# HF1R01.net
KiCad netlist of a schematic drawn in EAGLE
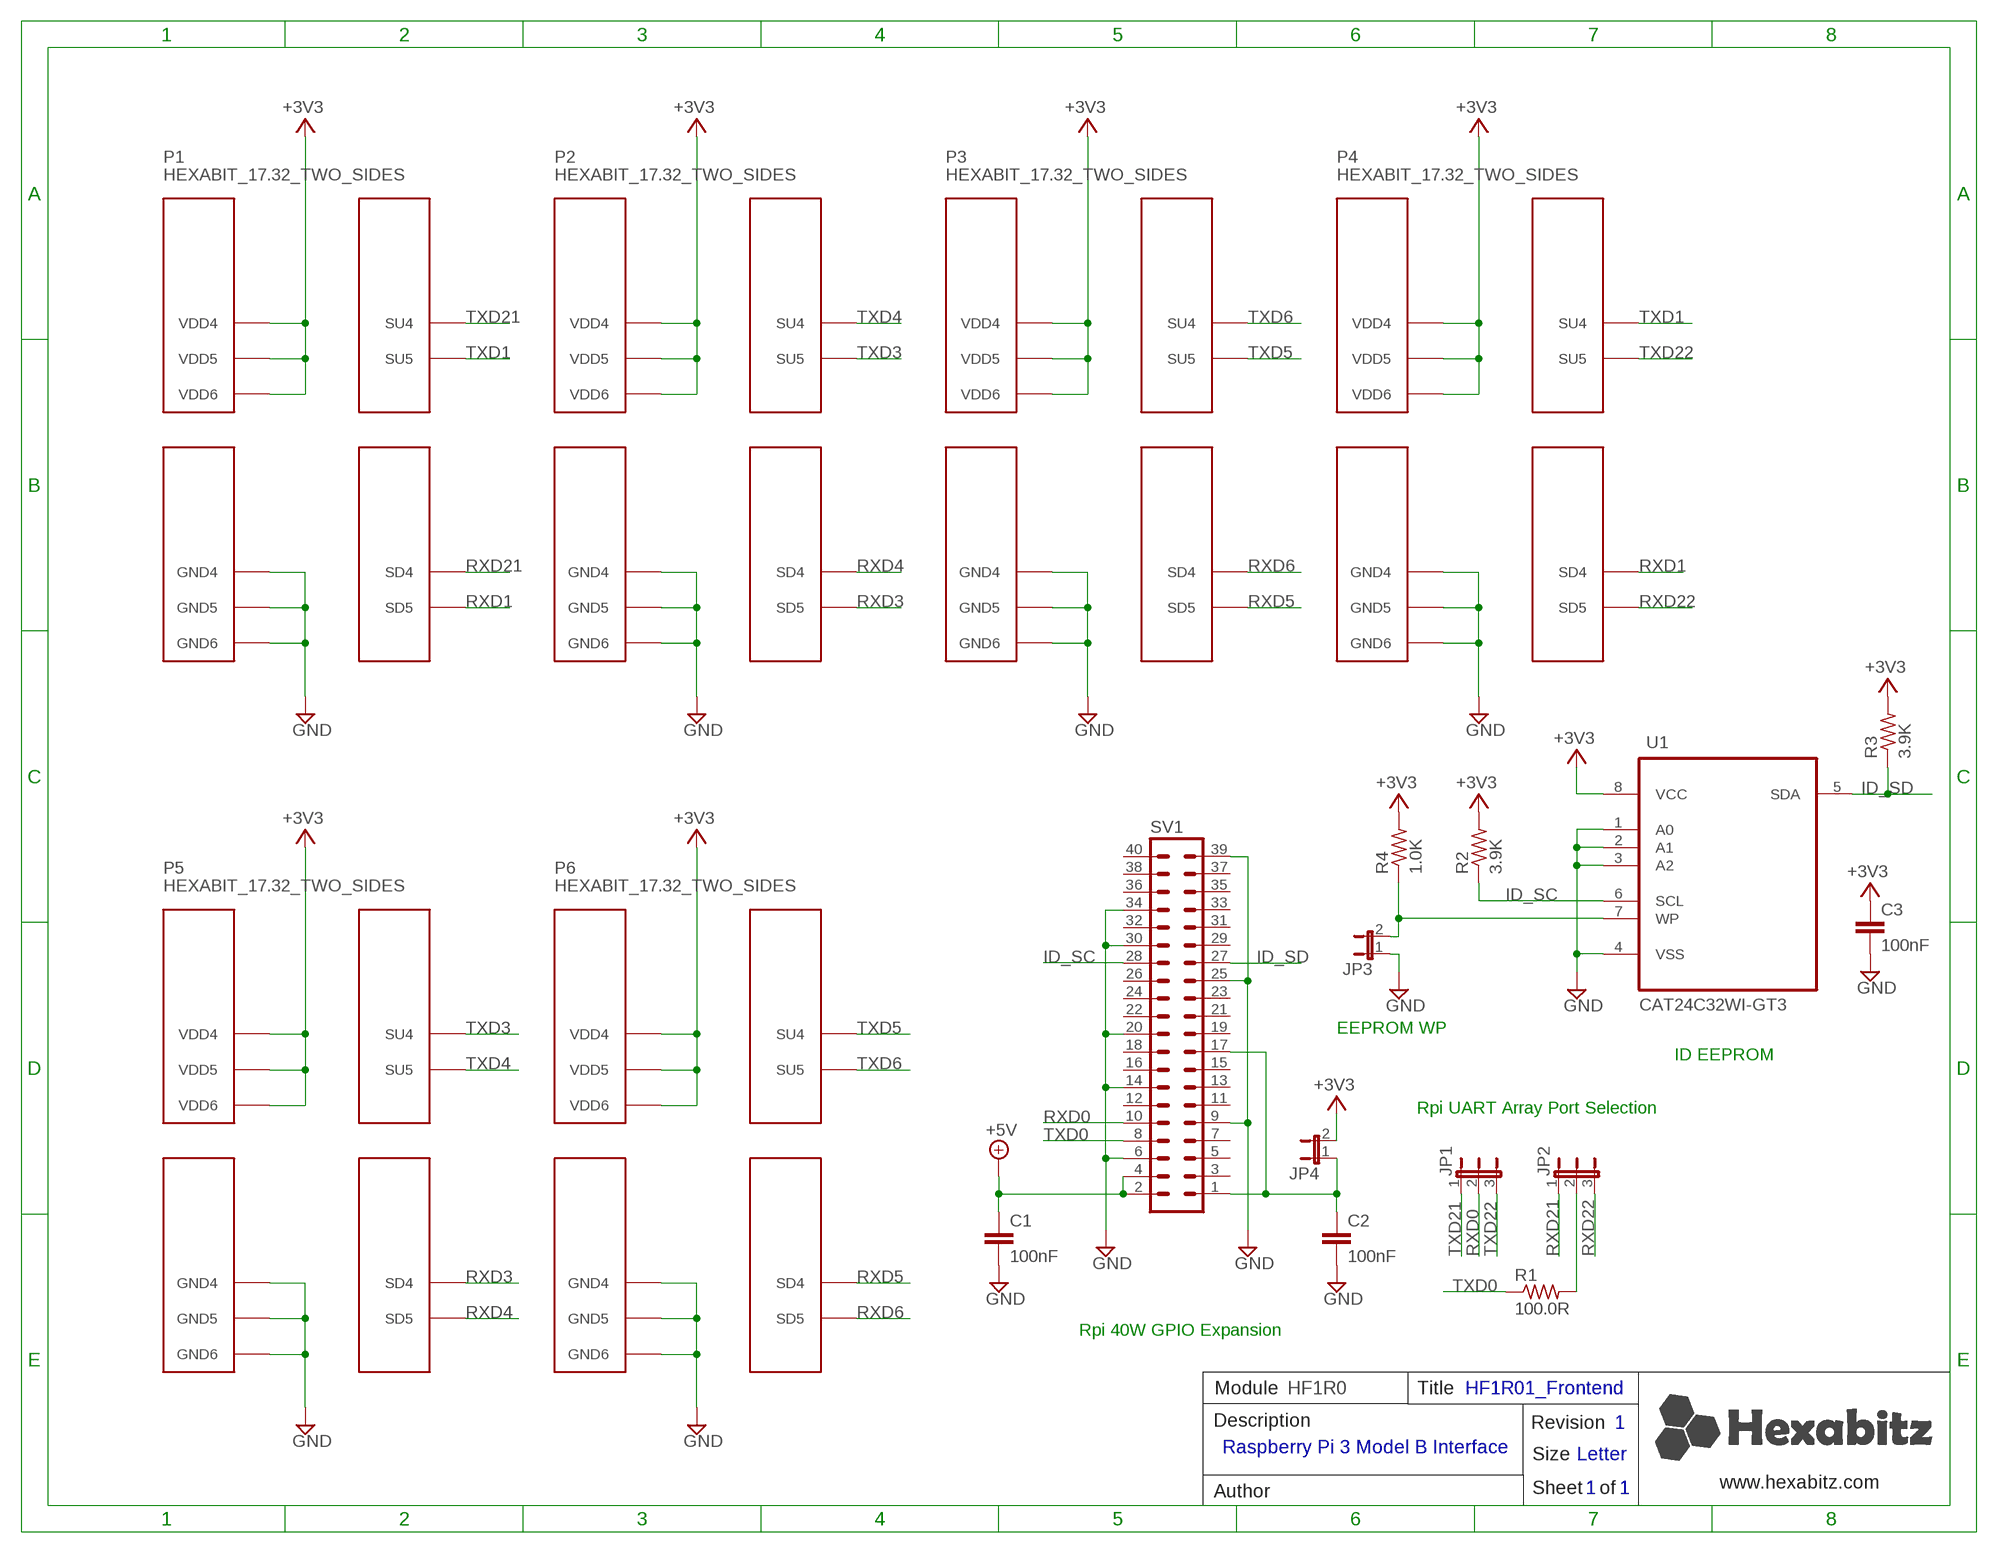
[diagram p0: schematic, sheet 1]

(export (version "E")
  (design (tool "Eeschema 10.0.6"))
  (components
    (comp (ref "C1")
      (value "100nF")
      (footprint "eagle-import:C-0603")
      (fields
        (field (name "CAPACITANCE") "100nF")
        (field (name "MFN") "KEMET")
        (field (name "MPN") "C0603C104K8RACTU")
        (field (name "OCTOPART_URL") "https://octopart.com/c0603c104k8ractu-kemet-145075?r=sp&s=9bS9ASSwSEqMCE9KBEQZ0g")
        (field (name "TOLERANCE") "10V")
        (field (name "VOLTAGE_RATING") "10%")
      )
      (libsource (lib "eagle-import") (part "C-0603"))
    )
    (comp (ref "C2")
      (value "100nF")
      (footprint "eagle-import:C-0603")
      (fields
        (field (name "CAPACITANCE") "100nF")
        (field (name "MFN") "KEMET")
        (field (name "MPN") "C0603C104K8RACTU")
        (field (name "OCTOPART_URL") "https://octopart.com/c0603c104k8ractu-kemet-145075?r=sp&s=9bS9ASSwSEqMCE9KBEQZ0g")
        (field (name "TOLERANCE") "10V")
        (field (name "VOLTAGE_RATING") "10%")
      )
      (libsource (lib "eagle-import") (part "C-0603"))
    )
    (comp (ref "C3")
      (value "100nF")
      (footprint "eagle-import:C-0603")
      (fields
        (field (name "CAPACITANCE") "100nF")
        (field (name "MFN") "KEMET")
        (field (name "MPN") "C0603C104K8RACTU")
        (field (name "OCTOPART_URL") "https://octopart.com/c0603c104k8ractu-kemet-145075?r=sp&s=9bS9ASSwSEqMCE9KBEQZ0g")
        (field (name "TOLERANCE") "10V")
        (field (name "VOLTAGE_RATING") "10%")
      )
      (libsource (lib "eagle-import") (part "C-0603"))
    )
    (comp (ref "JP1")
      (value "61300311121")
      (footprint "eagle-import:JP2")
      (libsource (lib "eagle-import") (part "JP2E"))
    )
    (comp (ref "JP2")
      (value "61300311121")
      (footprint "eagle-import:JP2")
      (libsource (lib "eagle-import") (part "JP2E"))
    )
    (comp (ref "JP3")
      (value "61300211121")
      (footprint "eagle-import:JP1")
      (libsource (lib "eagle-import") (part "JP1E"))
    )
    (comp (ref "JP4")
      (value "61300211121")
      (footprint "eagle-import:JP1")
      (libsource (lib "eagle-import") (part "JP1E"))
    )
    (comp (ref "P1")
      (value "HEXABIT_17.32_TWO_SIDES")
      (footprint "eagle-import:HEXABIT_17.32_TWO_SIDES")
      (libsource (lib "eagle-import") (part "HEXABIT_?_TWO_SIDES17.32"))
    )
    (comp (ref "P2")
      (value "HEXABIT_17.32_TWO_SIDES")
      (footprint "eagle-import:HEXABIT_17.32_TWO_SIDES")
      (libsource (lib "eagle-import") (part "HEXABIT_?_TWO_SIDES17.32"))
    )
    (comp (ref "P3")
      (value "HEXABIT_17.32_TWO_SIDES")
      (footprint "eagle-import:HEXABIT_17.32_TWO_SIDES")
      (libsource (lib "eagle-import") (part "HEXABIT_?_TWO_SIDES17.32"))
    )
    (comp (ref "P4")
      (value "HEXABIT_17.32_TWO_SIDES")
      (footprint "eagle-import:HEXABIT_17.32_TWO_SIDES")
      (libsource (lib "eagle-import") (part "HEXABIT_?_TWO_SIDES17.32"))
    )
    (comp (ref "P5")
      (value "HEXABIT_17.32_TWO_SIDES")
      (footprint "eagle-import:HEXABIT_17.32_TWO_SIDES")
      (libsource (lib "eagle-import") (part "HEXABIT_?_TWO_SIDES17.32"))
    )
    (comp (ref "P6")
      (value "HEXABIT_17.32_TWO_SIDES")
      (footprint "eagle-import:HEXABIT_17.32_TWO_SIDES")
      (libsource (lib "eagle-import") (part "HEXABIT_?_TWO_SIDES17.32"))
    )
    (comp (ref "R1")
      (value "100.0R")
      (footprint "eagle-import:R-0603")
      (fields
        (field (name "MFN") "Panasonic ")
        (field (name "MPN") "ERJ-PA3F1000V")
        (field (name "OCTOPART_URL") "https://octopart.com/erj-pa3f1000v-panasonic-51302178?r=sp&s=FtfQlVmZQ6G_o34px3VECw")
        (field (name "RESISTANCE") "100.0 Ohm")
        (field (name "TOLERANCE") "1%")
      )
      (libsource (lib "eagle-import") (part "R-0603"))
    )
    (comp (ref "R2")
      (value "3.9K")
      (footprint "eagle-import:R-0603")
      (fields
        (field (name "MFN") "Vishay")
        (field (name "MPN") "CRCW06033K90FKEA")
        (field (name "OCTOPART_URL") "https://octopart.com/crcw06033k90fkea-vishay-40019003?r=sp&s=g-tYgB-WSDSQxdPWmNeinA")
        (field (name "RESISTANCE") "3.9 kOhm")
        (field (name "TOLERANCE") "1%")
      )
      (libsource (lib "eagle-import") (part "R-0603"))
    )
    (comp (ref "R3")
      (value "3.9K")
      (footprint "eagle-import:R-0603")
      (fields
        (field (name "MFN") "Vishay")
        (field (name "MPN") "CRCW06033K90FKEA")
        (field (name "OCTOPART_URL") "https://octopart.com/crcw06033k90fkea-vishay-40019003?r=sp&s=g-tYgB-WSDSQxdPWmNeinA")
        (field (name "RESISTANCE") "3.9 kOhm")
        (field (name "TOLERANCE") "1%")
      )
      (libsource (lib "eagle-import") (part "R-0603"))
    )
    (comp (ref "R4")
      (value "1.0K")
      (footprint "eagle-import:R-0603")
      (fields
        (field (name "MFN") "Panasonic")
        (field (name "MPN") "ERJ-3EKF1001V")
        (field (name "OCTOPART_URL") "https://octopart.com/erj-3ekf1001v-panasonic-55403646?r=sp&s=_UtQAJDmTsiNho0Uqf11iA")
        (field (name "RESISTANCE") "1.0 kOhm")
        (field (name "TOLERANCE") "1%")
      )
      (libsource (lib "eagle-import") (part "R-0603"))
    )
    (comp (ref "SV1")
      (value "PPTC202LFBN-RC")
      (footprint "eagle-import:MA20-2")
      (fields (field (name "MF") " Sullins Connector Solutions") (field (name "MPN") "PPTC202LFBN-RC"))
      (libsource (lib "eagle-import") (part "MA20-2"))
    )
    (comp (ref "U1")
      (value "CAT24C32WI-GT3")
      (footprint "eagle-import:SOIC127P600X175-8N")
      (libsource (lib "eagle-import") (part "CAT24C32WI-GT3"))
    )
  )
  (nets
    (net (code "1") (name "+3V3") (class "Default")
      (node (ref "C3") (pin "1") (pinfunction "1_1") (pintype "passive"))
      (node (ref "JP4") (pin "2") (pinfunction "2_2") (pintype "passive"))
      (node (ref "P1") (pin "PAD_PU10") (pinfunction "VDD4_PAD_PU10") (pintype "power_in"))
      (node (ref "P1") (pin "PAD_PU11") (pinfunction "VDD5_PAD_PU11") (pintype "power_in"))
      (node (ref "P1") (pin "PAD_PU12") (pinfunction "VDD6_PAD_PU12") (pintype "power_in"))
      (node (ref "P2") (pin "PAD_PU10") (pinfunction "VDD4_PAD_PU10") (pintype "power_in"))
      (node (ref "P2") (pin "PAD_PU11") (pinfunction "VDD5_PAD_PU11") (pintype "power_in"))
      (node (ref "P2") (pin "PAD_PU12") (pinfunction "VDD6_PAD_PU12") (pintype "power_in"))
      (node (ref "P3") (pin "PAD_PU10") (pinfunction "VDD4_PAD_PU10") (pintype "power_in"))
      (node (ref "P3") (pin "PAD_PU11") (pinfunction "VDD5_PAD_PU11") (pintype "power_in"))
      (node (ref "P3") (pin "PAD_PU12") (pinfunction "VDD6_PAD_PU12") (pintype "power_in"))
      (node (ref "P4") (pin "PAD_PU10") (pinfunction "VDD4_PAD_PU10") (pintype "power_in"))
      (node (ref "P4") (pin "PAD_PU11") (pinfunction "VDD5_PAD_PU11") (pintype "power_in"))
      (node (ref "P4") (pin "PAD_PU12") (pinfunction "VDD6_PAD_PU12") (pintype "power_in"))
      (node (ref "P5") (pin "PAD_PU10") (pinfunction "VDD4_PAD_PU10") (pintype "power_in"))
      (node (ref "P5") (pin "PAD_PU11") (pinfunction "VDD5_PAD_PU11") (pintype "power_in"))
      (node (ref "P5") (pin "PAD_PU12") (pinfunction "VDD6_PAD_PU12") (pintype "power_in"))
      (node (ref "P6") (pin "PAD_PU10") (pinfunction "VDD4_PAD_PU10") (pintype "power_in"))
      (node (ref "P6") (pin "PAD_PU11") (pinfunction "VDD5_PAD_PU11") (pintype "power_in"))
      (node (ref "P6") (pin "PAD_PU12") (pinfunction "VDD6_PAD_PU12") (pintype "power_in"))
      (node (ref "R2") (pin "2") (pinfunction "2_2") (pintype "passive"))
      (node (ref "R3") (pin "2") (pinfunction "2_2") (pintype "passive"))
      (node (ref "R4") (pin "2") (pinfunction "2_2") (pintype "passive"))
      (node (ref "U1") (pin "8") (pinfunction "VCC_8") (pintype "power_in"))
    )
    (net (code "2") (name "+5V") (class "Default")
      (node (ref "C1") (pin "1") (pinfunction "1_1") (pintype "passive"))
      (node (ref "SV1") (pin "2") (pinfunction "2_2") (pintype "passive"))
      (node (ref "SV1") (pin "4") (pinfunction "4_4") (pintype "passive"))
    )
    (net (code "3") (name "/ID_SC") (class "Default")
      (node (ref "R2") (pin "1") (pinfunction "1_1") (pintype "passive"))
      (node (ref "SV1") (pin "28") (pinfunction "28_28") (pintype "passive"))
      (node (ref "U1") (pin "6") (pinfunction "SCL_6") (pintype "input"))
    )
    (net (code "4") (name "/ID_SD") (class "Default")
      (node (ref "R3") (pin "1") (pinfunction "1_1") (pintype "passive"))
      (node (ref "SV1") (pin "27") (pinfunction "27_27") (pintype "passive"))
      (node (ref "U1") (pin "5") (pinfunction "SDA_5") (pintype "bidirectional"))
    )
    (net (code "5") (name "/RXD0") (class "Default")
      (node (ref "JP1") (pin "2") (pinfunction "2_2") (pintype "passive"))
      (node (ref "SV1") (pin "10") (pinfunction "10_10") (pintype "passive"))
    )
    (net (code "6") (name "/RXD1") (class "Default")
      (node (ref "P1") (pin "PAD_PD5") (pinfunction "SD5_PAD_PD5") (pintype "bidirectional"))
      (node (ref "P4") (pin "PAD_PD4") (pinfunction "SD4_PAD_PD4") (pintype "bidirectional"))
    )
    (net (code "7") (name "/RXD3") (class "Default")
      (node (ref "P2") (pin "PAD_PD5") (pinfunction "SD5_PAD_PD5") (pintype "bidirectional"))
      (node (ref "P5") (pin "PAD_PD4") (pinfunction "SD4_PAD_PD4") (pintype "bidirectional"))
    )
    (net (code "8") (name "/RXD4") (class "Default")
      (node (ref "P2") (pin "PAD_PD4") (pinfunction "SD4_PAD_PD4") (pintype "bidirectional"))
      (node (ref "P5") (pin "PAD_PD5") (pinfunction "SD5_PAD_PD5") (pintype "bidirectional"))
    )
    (net (code "9") (name "/RXD5") (class "Default")
      (node (ref "P3") (pin "PAD_PD5") (pinfunction "SD5_PAD_PD5") (pintype "bidirectional"))
      (node (ref "P6") (pin "PAD_PD4") (pinfunction "SD4_PAD_PD4") (pintype "bidirectional"))
    )
    (net (code "10") (name "/RXD6") (class "Default")
      (node (ref "P3") (pin "PAD_PD4") (pinfunction "SD4_PAD_PD4") (pintype "bidirectional"))
      (node (ref "P6") (pin "PAD_PD5") (pinfunction "SD5_PAD_PD5") (pintype "bidirectional"))
    )
    (net (code "11") (name "/RXD21") (class "Default")
      (node (ref "JP2") (pin "1") (pinfunction "1_1") (pintype "passive"))
      (node (ref "P1") (pin "PAD_PD4") (pinfunction "SD4_PAD_PD4") (pintype "bidirectional"))
    )
    (net (code "12") (name "/RXD22") (class "Default")
      (node (ref "JP2") (pin "3") (pinfunction "3_3") (pintype "passive"))
      (node (ref "P4") (pin "PAD_PD5") (pinfunction "SD5_PAD_PD5") (pintype "bidirectional"))
    )
    (net (code "13") (name "/TXD0") (class "Default")
      (node (ref "R1") (pin "1") (pinfunction "1_1") (pintype "passive"))
      (node (ref "SV1") (pin "8") (pinfunction "8_8") (pintype "passive"))
    )
    (net (code "14") (name "/TXD1") (class "Default")
      (node (ref "P1") (pin "PAD_PU5") (pinfunction "SU5_PAD_PU5") (pintype "bidirectional"))
      (node (ref "P4") (pin "PAD_PU4") (pinfunction "SU4_PAD_PU4") (pintype "bidirectional"))
    )
    (net (code "15") (name "/TXD3") (class "Default")
      (node (ref "P2") (pin "PAD_PU5") (pinfunction "SU5_PAD_PU5") (pintype "bidirectional"))
      (node (ref "P5") (pin "PAD_PU4") (pinfunction "SU4_PAD_PU4") (pintype "bidirectional"))
    )
    (net (code "16") (name "/TXD4") (class "Default")
      (node (ref "P2") (pin "PAD_PU4") (pinfunction "SU4_PAD_PU4") (pintype "bidirectional"))
      (node (ref "P5") (pin "PAD_PU5") (pinfunction "SU5_PAD_PU5") (pintype "bidirectional"))
    )
    (net (code "17") (name "/TXD5") (class "Default")
      (node (ref "P3") (pin "PAD_PU5") (pinfunction "SU5_PAD_PU5") (pintype "bidirectional"))
      (node (ref "P6") (pin "PAD_PU4") (pinfunction "SU4_PAD_PU4") (pintype "bidirectional"))
    )
    (net (code "18") (name "/TXD6") (class "Default")
      (node (ref "P3") (pin "PAD_PU4") (pinfunction "SU4_PAD_PU4") (pintype "bidirectional"))
      (node (ref "P6") (pin "PAD_PU5") (pinfunction "SU5_PAD_PU5") (pintype "bidirectional"))
    )
    (net (code "19") (name "/TXD21") (class "Default")
      (node (ref "JP1") (pin "1") (pinfunction "1_1") (pintype "passive"))
      (node (ref "P1") (pin "PAD_PU4") (pinfunction "SU4_PAD_PU4") (pintype "bidirectional"))
    )
    (net (code "20") (name "/TXD22") (class "Default")
      (node (ref "JP1") (pin "3") (pinfunction "3_3") (pintype "passive"))
      (node (ref "P4") (pin "PAD_PU5") (pinfunction "SU5_PAD_PU5") (pintype "bidirectional"))
    )
    (net (code "21") (name "GND") (class "Default")
      (node (ref "C1") (pin "2") (pinfunction "2_2") (pintype "passive"))
      (node (ref "C2") (pin "2") (pinfunction "2_2") (pintype "passive"))
      (node (ref "C3") (pin "2") (pinfunction "2_2") (pintype "passive"))
      (node (ref "JP3") (pin "1") (pinfunction "1_1") (pintype "passive"))
      (node (ref "P1") (pin "PAD_PD10") (pinfunction "GND4_PAD_PD10") (pintype "power_in"))
      (node (ref "P1") (pin "PAD_PD11") (pinfunction "GND5_PAD_PD11") (pintype "power_in"))
      (node (ref "P1") (pin "PAD_PD12") (pinfunction "GND6_PAD_PD12") (pintype "power_in"))
      (node (ref "P2") (pin "PAD_PD10") (pinfunction "GND4_PAD_PD10") (pintype "power_in"))
      (node (ref "P2") (pin "PAD_PD11") (pinfunction "GND5_PAD_PD11") (pintype "power_in"))
      (node (ref "P2") (pin "PAD_PD12") (pinfunction "GND6_PAD_PD12") (pintype "power_in"))
      (node (ref "P3") (pin "PAD_PD10") (pinfunction "GND4_PAD_PD10") (pintype "power_in"))
      (node (ref "P3") (pin "PAD_PD11") (pinfunction "GND5_PAD_PD11") (pintype "power_in"))
      (node (ref "P3") (pin "PAD_PD12") (pinfunction "GND6_PAD_PD12") (pintype "power_in"))
      (node (ref "P4") (pin "PAD_PD10") (pinfunction "GND4_PAD_PD10") (pintype "power_in"))
      (node (ref "P4") (pin "PAD_PD11") (pinfunction "GND5_PAD_PD11") (pintype "power_in"))
      (node (ref "P4") (pin "PAD_PD12") (pinfunction "GND6_PAD_PD12") (pintype "power_in"))
      (node (ref "P5") (pin "PAD_PD10") (pinfunction "GND4_PAD_PD10") (pintype "power_in"))
      (node (ref "P5") (pin "PAD_PD11") (pinfunction "GND5_PAD_PD11") (pintype "power_in"))
      (node (ref "P5") (pin "PAD_PD12") (pinfunction "GND6_PAD_PD12") (pintype "power_in"))
      (node (ref "P6") (pin "PAD_PD10") (pinfunction "GND4_PAD_PD10") (pintype "power_in"))
      (node (ref "P6") (pin "PAD_PD11") (pinfunction "GND5_PAD_PD11") (pintype "power_in"))
      (node (ref "P6") (pin "PAD_PD12") (pinfunction "GND6_PAD_PD12") (pintype "power_in"))
      (node (ref "SV1") (pin "14") (pinfunction "14_14") (pintype "passive"))
      (node (ref "SV1") (pin "20") (pinfunction "20_20") (pintype "passive"))
      (node (ref "SV1") (pin "25") (pinfunction "25_25") (pintype "passive"))
      (node (ref "SV1") (pin "30") (pinfunction "30_30") (pintype "passive"))
      (node (ref "SV1") (pin "34") (pinfunction "34_34") (pintype "passive"))
      (node (ref "SV1") (pin "39") (pinfunction "39_39") (pintype "passive"))
      (node (ref "SV1") (pin "6") (pinfunction "6_6") (pintype "passive"))
      (node (ref "SV1") (pin "9") (pinfunction "9_9") (pintype "passive"))
      (node (ref "U1") (pin "1") (pinfunction "A0_1") (pintype "input"))
      (node (ref "U1") (pin "2") (pinfunction "A1_2") (pintype "input"))
      (node (ref "U1") (pin "3") (pinfunction "A2_3") (pintype "input"))
      (node (ref "U1") (pin "4") (pinfunction "VSS_4") (pintype "passive"))
    )
    (net (code "22") (name "Net-(C2-Pad1)") (class "Default")
      (node (ref "C2") (pin "1") (pinfunction "1_1") (pintype "passive"))
      (node (ref "JP4") (pin "1") (pinfunction "1_1") (pintype "passive"))
      (node (ref "SV1") (pin "1") (pinfunction "1_1") (pintype "passive"))
      (node (ref "SV1") (pin "17") (pinfunction "17_17") (pintype "passive"))
    )
    (net (code "23") (name "Net-(JP2-Pad2)") (class "Default")
      (node (ref "JP2") (pin "2") (pinfunction "2_2") (pintype "passive"))
      (node (ref "R1") (pin "2") (pinfunction "2_2") (pintype "passive"))
    )
    (net (code "24") (name "Net-(U1-WP)") (class "Default")
      (node (ref "JP3") (pin "2") (pinfunction "2_2") (pintype "passive"))
      (node (ref "R4") (pin "1") (pinfunction "1_1") (pintype "passive"))
      (node (ref "U1") (pin "7") (pinfunction "WP_7") (pintype "input"))
    )
    (net (code "25") (name "unconnected-(SV1-Pad3)") (class "Default")
      (node (ref "SV1") (pin "3") (pinfunction "3_3") (pintype "passive"))
    )
    (net (code "26") (name "unconnected-(SV1-Pad5)") (class "Default")
      (node (ref "SV1") (pin "5") (pinfunction "5_5") (pintype "passive"))
    )
    (net (code "27") (name "unconnected-(SV1-Pad7)") (class "Default")
      (node (ref "SV1") (pin "7") (pinfunction "7_7") (pintype "passive"))
    )
    (net (code "28") (name "unconnected-(SV1-Pad11)") (class "Default")
      (node (ref "SV1") (pin "11") (pinfunction "11_11") (pintype "passive"))
    )
    (net (code "29") (name "unconnected-(SV1-Pad12)") (class "Default")
      (node (ref "SV1") (pin "12") (pinfunction "12_12") (pintype "passive"))
    )
    (net (code "30") (name "unconnected-(SV1-Pad13)") (class "Default")
      (node (ref "SV1") (pin "13") (pinfunction "13_13") (pintype "passive"))
    )
    (net (code "31") (name "unconnected-(SV1-Pad15)") (class "Default")
      (node (ref "SV1") (pin "15") (pinfunction "15_15") (pintype "passive"))
    )
    (net (code "32") (name "unconnected-(SV1-Pad16)") (class "Default")
      (node (ref "SV1") (pin "16") (pinfunction "16_16") (pintype "passive"))
    )
    (net (code "33") (name "unconnected-(SV1-Pad18)") (class "Default")
      (node (ref "SV1") (pin "18") (pinfunction "18_18") (pintype "passive"))
    )
    (net (code "34") (name "unconnected-(SV1-Pad19)") (class "Default")
      (node (ref "SV1") (pin "19") (pinfunction "19_19") (pintype "passive"))
    )
    (net (code "35") (name "unconnected-(SV1-Pad21)") (class "Default")
      (node (ref "SV1") (pin "21") (pinfunction "21_21") (pintype "passive"))
    )
    (net (code "36") (name "unconnected-(SV1-Pad22)") (class "Default")
      (node (ref "SV1") (pin "22") (pinfunction "22_22") (pintype "passive"))
    )
    (net (code "37") (name "unconnected-(SV1-Pad23)") (class "Default")
      (node (ref "SV1") (pin "23") (pinfunction "23_23") (pintype "passive"))
    )
    (net (code "38") (name "unconnected-(SV1-Pad24)") (class "Default")
      (node (ref "SV1") (pin "24") (pinfunction "24_24") (pintype "passive"))
    )
    (net (code "39") (name "unconnected-(SV1-Pad26)") (class "Default")
      (node (ref "SV1") (pin "26") (pinfunction "26_26") (pintype "passive"))
    )
    (net (code "40") (name "unconnected-(SV1-Pad29)") (class "Default")
      (node (ref "SV1") (pin "29") (pinfunction "29_29") (pintype "passive"))
    )
    (net (code "41") (name "unconnected-(SV1-Pad31)") (class "Default")
      (node (ref "SV1") (pin "31") (pinfunction "31_31") (pintype "passive"))
    )
    (net (code "42") (name "unconnected-(SV1-Pad32)") (class "Default")
      (node (ref "SV1") (pin "32") (pinfunction "32_32") (pintype "passive"))
    )
    (net (code "43") (name "unconnected-(SV1-Pad33)") (class "Default")
      (node (ref "SV1") (pin "33") (pinfunction "33_33") (pintype "passive"))
    )
    (net (code "44") (name "unconnected-(SV1-Pad35)") (class "Default")
      (node (ref "SV1") (pin "35") (pinfunction "35_35") (pintype "passive"))
    )
    (net (code "45") (name "unconnected-(SV1-Pad36)") (class "Default")
      (node (ref "SV1") (pin "36") (pinfunction "36_36") (pintype "passive"))
    )
    (net (code "46") (name "unconnected-(SV1-Pad37)") (class "Default")
      (node (ref "SV1") (pin "37") (pinfunction "37_37") (pintype "passive"))
    )
    (net (code "47") (name "unconnected-(SV1-Pad38)") (class "Default")
      (node (ref "SV1") (pin "38") (pinfunction "38_38") (pintype "passive"))
    )
    (net (code "48") (name "unconnected-(SV1-Pad40)") (class "Default")
      (node (ref "SV1") (pin "40") (pinfunction "40_40") (pintype "passive"))
    )
  )
)
